# Backplane_extRefV2.net
KiCad netlist of a schematic drawn in EAGLE
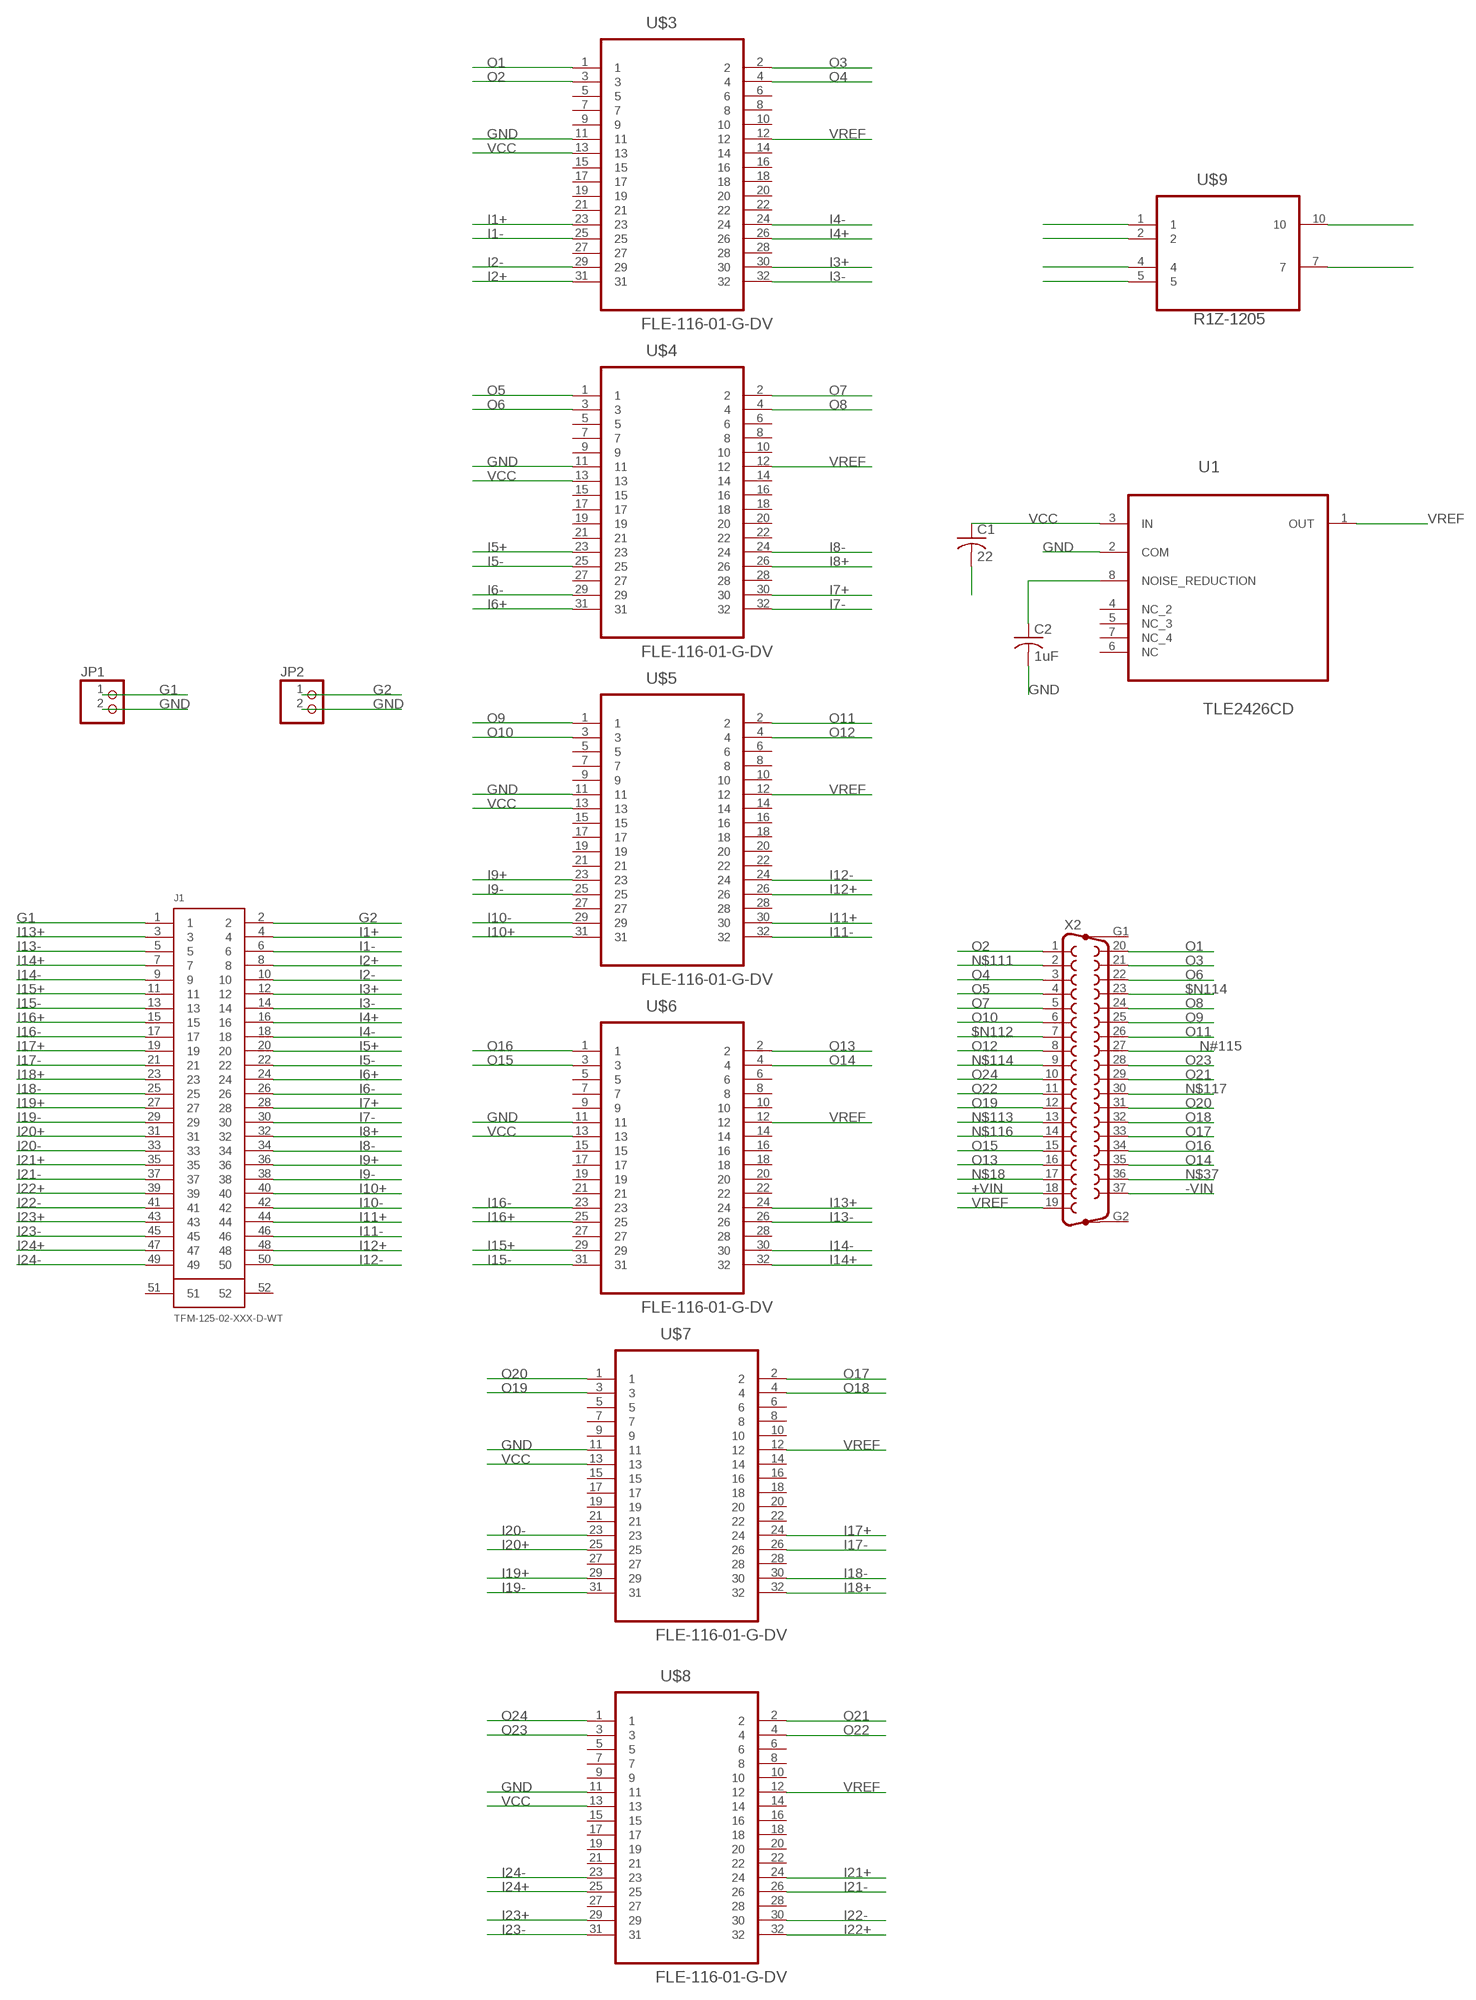
[diagram p0: schematic, sheet 1]

(export (version "E")
  (design (tool "Eeschema 10.0.6"))
  (components
    (comp (ref "C1")
      (value "22")
      (footprint "eagle-import:C0805")
      (libsource (lib "eagle-import") (part "C-USC0805"))
    )
    (comp (ref "C2")
      (value "1uF")
      (footprint "eagle-import:C0805")
      (libsource (lib "eagle-import") (part "C-USC0805"))
    )
    (comp (ref "J1")
      (value "TFM-125-02-XXX-D-WT")
      (footprint "eagle-import:TFM-125-02-XXX-D-WT")
      (libsource (lib "eagle-import") (part "TFM-125-02-XXX-D-WT"))
    )
    (comp (ref "JP1")
      (value "PINHD-1X2")
      (footprint "eagle-import:1X02")
      (libsource (lib "eagle-import") (part "PINHD-1X2"))
    )
    (comp (ref "JP2")
      (value "PINHD-1X2")
      (footprint "eagle-import:1X02")
      (libsource (lib "eagle-import") (part "PINHD-1X2"))
    )
    (comp (ref "U$3")
      (value "FLE-116-01-G-DV")
      (footprint "eagle-import:SAMTEC_FLE-116-01-G-DV")
      (libsource (lib "eagle-import") (part "FLE-116-01-G-DV"))
    )
    (comp (ref "U$4")
      (value "FLE-116-01-G-DV")
      (footprint "eagle-import:SAMTEC_FLE-116-01-G-DV")
      (libsource (lib "eagle-import") (part "FLE-116-01-G-DV"))
    )
    (comp (ref "U$5")
      (value "FLE-116-01-G-DV")
      (footprint "eagle-import:SAMTEC_FLE-116-01-G-DV")
      (libsource (lib "eagle-import") (part "FLE-116-01-G-DV"))
    )
    (comp (ref "U$6")
      (value "FLE-116-01-G-DV")
      (footprint "eagle-import:SAMTEC_FLE-116-01-G-DV")
      (libsource (lib "eagle-import") (part "FLE-116-01-G-DV"))
    )
    (comp (ref "U$7")
      (value "FLE-116-01-G-DV")
      (footprint "eagle-import:SAMTEC_FLE-116-01-G-DV")
      (libsource (lib "eagle-import") (part "FLE-116-01-G-DV"))
    )
    (comp (ref "U$8")
      (value "FLE-116-01-G-DV")
      (footprint "eagle-import:SAMTEC_FLE-116-01-G-DV")
      (libsource (lib "eagle-import") (part "FLE-116-01-G-DV"))
    )
    (comp (ref "U$9")
      (value "R1Z-1205")
      (footprint "eagle-import:R1Z-1205")
      (libsource (lib "eagle-import") (part "R1Z-1205"))
    )
    (comp (ref "U1")
      (value "TLE2426CD")
      (footprint "eagle-import:SOIC127P600X175-8N")
      (libsource (lib "eagle-import") (part "TLE2426CD"))
    )
    (comp (ref "X2")
      (value "F37HP")
      (footprint "eagle-import:F37HP")
      (libsource (lib "eagle-import") (part "F37HP"))
    )
  )
  (nets
    (net (code "1") (name "/$N112") (class "Default")
      (node (ref "X2") (pin "7") (pinfunction "7_7") (pintype "passive"))
    )
    (net (code "2") (name "/$N114") (class "Default")
      (node (ref "X2") (pin "23") (pinfunction "23_23") (pintype "passive"))
    )
    (net (code "3") (name "/+VIN") (class "Default")
      (node (ref "U$9") (pin "2") (pinfunction "2_2") (pintype "passive"))
      (node (ref "X2") (pin "18") (pinfunction "18_18") (pintype "passive"))
    )
    (net (code "4") (name "/-VIN") (class "Default")
      (node (ref "U$9") (pin "1") (pinfunction "1_1") (pintype "passive"))
      (node (ref "X2") (pin "37") (pinfunction "37_37") (pintype "passive"))
    )
    (net (code "5") (name "/G1") (class "Default")
      (node (ref "J1") (pin "1") (pinfunction "1_1") (pintype "bidirectional"))
      (node (ref "JP1") (pin "1") (pinfunction "1_1") (pintype "passive"))
    )
    (net (code "6") (name "/G2") (class "Default")
      (node (ref "J1") (pin "2") (pinfunction "2_2") (pintype "bidirectional"))
      (node (ref "JP2") (pin "1") (pinfunction "1_1") (pintype "passive"))
    )
    (net (code "7") (name "/GND") (class "Default")
      (node (ref "C1") (pin "2") (pinfunction "2_2") (pintype "passive"))
      (node (ref "C2") (pin "2") (pinfunction "2_2") (pintype "passive"))
      (node (ref "JP1") (pin "2") (pinfunction "2_2") (pintype "passive"))
      (node (ref "JP2") (pin "2") (pinfunction "2_2") (pintype "passive"))
      (node (ref "U$3") (pin "11") (pinfunction "11_11") (pintype "passive"))
      (node (ref "U$4") (pin "11") (pinfunction "11_11") (pintype "passive"))
      (node (ref "U$5") (pin "11") (pinfunction "11_11") (pintype "passive"))
      (node (ref "U$6") (pin "11") (pinfunction "11_11") (pintype "passive"))
      (node (ref "U$7") (pin "11") (pinfunction "11_11") (pintype "passive"))
      (node (ref "U$8") (pin "11") (pinfunction "11_11") (pintype "passive"))
      (node (ref "U$9") (pin "4") (pinfunction "4_4") (pintype "passive"))
      (node (ref "U$9") (pin "5") (pinfunction "5_5") (pintype "passive"))
      (node (ref "U1") (pin "2") (pinfunction "COM_2") (pintype "passive"))
    )
    (net (code "8") (name "/I1+") (class "Default")
      (node (ref "J1") (pin "4") (pinfunction "4_4") (pintype "bidirectional"))
      (node (ref "U$3") (pin "23") (pinfunction "23_23") (pintype "passive"))
    )
    (net (code "9") (name "/I1-") (class "Default")
      (node (ref "J1") (pin "6") (pinfunction "6_6") (pintype "bidirectional"))
      (node (ref "U$3") (pin "25") (pinfunction "25_25") (pintype "passive"))
    )
    (net (code "10") (name "/I2+") (class "Default")
      (node (ref "J1") (pin "8") (pinfunction "8_8") (pintype "bidirectional"))
      (node (ref "U$3") (pin "31") (pinfunction "31_31") (pintype "passive"))
    )
    (net (code "11") (name "/I2-") (class "Default")
      (node (ref "J1") (pin "10") (pinfunction "10_10") (pintype "bidirectional"))
      (node (ref "U$3") (pin "29") (pinfunction "29_29") (pintype "passive"))
    )
    (net (code "12") (name "/I3+") (class "Default")
      (node (ref "J1") (pin "12") (pinfunction "12_12") (pintype "bidirectional"))
      (node (ref "U$3") (pin "30") (pinfunction "30_30") (pintype "passive"))
    )
    (net (code "13") (name "/I3-") (class "Default")
      (node (ref "J1") (pin "14") (pinfunction "14_14") (pintype "bidirectional"))
      (node (ref "U$3") (pin "32") (pinfunction "32_32") (pintype "passive"))
    )
    (net (code "14") (name "/I4+") (class "Default")
      (node (ref "J1") (pin "16") (pinfunction "16_16") (pintype "bidirectional"))
      (node (ref "U$3") (pin "26") (pinfunction "26_26") (pintype "passive"))
    )
    (net (code "15") (name "/I4-") (class "Default")
      (node (ref "J1") (pin "18") (pinfunction "18_18") (pintype "bidirectional"))
      (node (ref "U$3") (pin "24") (pinfunction "24_24") (pintype "passive"))
    )
    (net (code "16") (name "/I5+") (class "Default")
      (node (ref "J1") (pin "20") (pinfunction "20_20") (pintype "bidirectional"))
      (node (ref "U$4") (pin "23") (pinfunction "23_23") (pintype "passive"))
    )
    (net (code "17") (name "/I5-") (class "Default")
      (node (ref "J1") (pin "22") (pinfunction "22_22") (pintype "bidirectional"))
      (node (ref "U$4") (pin "25") (pinfunction "25_25") (pintype "passive"))
    )
    (net (code "18") (name "/I6+") (class "Default")
      (node (ref "J1") (pin "24") (pinfunction "24_24") (pintype "bidirectional"))
      (node (ref "U$4") (pin "31") (pinfunction "31_31") (pintype "passive"))
    )
    (net (code "19") (name "/I6-") (class "Default")
      (node (ref "J1") (pin "26") (pinfunction "26_26") (pintype "bidirectional"))
      (node (ref "U$4") (pin "29") (pinfunction "29_29") (pintype "passive"))
    )
    (net (code "20") (name "/I7+") (class "Default")
      (node (ref "J1") (pin "28") (pinfunction "28_28") (pintype "bidirectional"))
      (node (ref "U$4") (pin "30") (pinfunction "30_30") (pintype "passive"))
    )
    (net (code "21") (name "/I7-") (class "Default")
      (node (ref "J1") (pin "30") (pinfunction "30_30") (pintype "bidirectional"))
      (node (ref "U$4") (pin "32") (pinfunction "32_32") (pintype "passive"))
    )
    (net (code "22") (name "/I8+") (class "Default")
      (node (ref "J1") (pin "32") (pinfunction "32_32") (pintype "bidirectional"))
      (node (ref "U$4") (pin "26") (pinfunction "26_26") (pintype "passive"))
    )
    (net (code "23") (name "/I8-") (class "Default")
      (node (ref "J1") (pin "34") (pinfunction "34_34") (pintype "bidirectional"))
      (node (ref "U$4") (pin "24") (pinfunction "24_24") (pintype "passive"))
    )
    (net (code "24") (name "/I9+") (class "Default")
      (node (ref "J1") (pin "36") (pinfunction "36_36") (pintype "bidirectional"))
      (node (ref "U$5") (pin "23") (pinfunction "23_23") (pintype "passive"))
    )
    (net (code "25") (name "/I9-") (class "Default")
      (node (ref "J1") (pin "38") (pinfunction "38_38") (pintype "bidirectional"))
      (node (ref "U$5") (pin "25") (pinfunction "25_25") (pintype "passive"))
    )
    (net (code "26") (name "/I10+") (class "Default")
      (node (ref "J1") (pin "40") (pinfunction "40_40") (pintype "bidirectional"))
      (node (ref "U$5") (pin "31") (pinfunction "31_31") (pintype "passive"))
    )
    (net (code "27") (name "/I10-") (class "Default")
      (node (ref "J1") (pin "42") (pinfunction "42_42") (pintype "bidirectional"))
      (node (ref "U$5") (pin "29") (pinfunction "29_29") (pintype "passive"))
    )
    (net (code "28") (name "/I11+") (class "Default")
      (node (ref "J1") (pin "44") (pinfunction "44_44") (pintype "bidirectional"))
      (node (ref "U$5") (pin "30") (pinfunction "30_30") (pintype "passive"))
    )
    (net (code "29") (name "/I11-") (class "Default")
      (node (ref "J1") (pin "46") (pinfunction "46_46") (pintype "bidirectional"))
      (node (ref "U$5") (pin "32") (pinfunction "32_32") (pintype "passive"))
    )
    (net (code "30") (name "/I12+") (class "Default")
      (node (ref "J1") (pin "48") (pinfunction "48_48") (pintype "bidirectional"))
      (node (ref "U$5") (pin "26") (pinfunction "26_26") (pintype "passive"))
    )
    (net (code "31") (name "/I12-") (class "Default")
      (node (ref "J1") (pin "50") (pinfunction "50_50") (pintype "bidirectional"))
      (node (ref "U$5") (pin "24") (pinfunction "24_24") (pintype "passive"))
    )
    (net (code "32") (name "/I13+") (class "Default")
      (node (ref "J1") (pin "3") (pinfunction "3_3") (pintype "bidirectional"))
      (node (ref "U$6") (pin "24") (pinfunction "24_24") (pintype "passive"))
    )
    (net (code "33") (name "/I13-") (class "Default")
      (node (ref "J1") (pin "5") (pinfunction "5_5") (pintype "bidirectional"))
      (node (ref "U$6") (pin "26") (pinfunction "26_26") (pintype "passive"))
    )
    (net (code "34") (name "/I14+") (class "Default")
      (node (ref "J1") (pin "7") (pinfunction "7_7") (pintype "bidirectional"))
      (node (ref "U$6") (pin "32") (pinfunction "32_32") (pintype "passive"))
    )
    (net (code "35") (name "/I14-") (class "Default")
      (node (ref "J1") (pin "9") (pinfunction "9_9") (pintype "bidirectional"))
      (node (ref "U$6") (pin "30") (pinfunction "30_30") (pintype "passive"))
    )
    (net (code "36") (name "/I15+") (class "Default")
      (node (ref "J1") (pin "11") (pinfunction "11_11") (pintype "bidirectional"))
      (node (ref "U$6") (pin "29") (pinfunction "29_29") (pintype "passive"))
    )
    (net (code "37") (name "/I15-") (class "Default")
      (node (ref "J1") (pin "13") (pinfunction "13_13") (pintype "bidirectional"))
      (node (ref "U$6") (pin "31") (pinfunction "31_31") (pintype "passive"))
    )
    (net (code "38") (name "/I16+") (class "Default")
      (node (ref "J1") (pin "15") (pinfunction "15_15") (pintype "bidirectional"))
      (node (ref "U$6") (pin "25") (pinfunction "25_25") (pintype "passive"))
    )
    (net (code "39") (name "/I16-") (class "Default")
      (node (ref "J1") (pin "17") (pinfunction "17_17") (pintype "bidirectional"))
      (node (ref "U$6") (pin "23") (pinfunction "23_23") (pintype "passive"))
    )
    (net (code "40") (name "/I17+") (class "Default")
      (node (ref "J1") (pin "19") (pinfunction "19_19") (pintype "bidirectional"))
      (node (ref "U$7") (pin "24") (pinfunction "24_24") (pintype "passive"))
    )
    (net (code "41") (name "/I17-") (class "Default")
      (node (ref "J1") (pin "21") (pinfunction "21_21") (pintype "bidirectional"))
      (node (ref "U$7") (pin "26") (pinfunction "26_26") (pintype "passive"))
    )
    (net (code "42") (name "/I18+") (class "Default")
      (node (ref "J1") (pin "23") (pinfunction "23_23") (pintype "bidirectional"))
      (node (ref "U$7") (pin "32") (pinfunction "32_32") (pintype "passive"))
    )
    (net (code "43") (name "/I18-") (class "Default")
      (node (ref "J1") (pin "25") (pinfunction "25_25") (pintype "bidirectional"))
      (node (ref "U$7") (pin "30") (pinfunction "30_30") (pintype "passive"))
    )
    (net (code "44") (name "/I19+") (class "Default")
      (node (ref "J1") (pin "27") (pinfunction "27_27") (pintype "bidirectional"))
      (node (ref "U$7") (pin "29") (pinfunction "29_29") (pintype "passive"))
    )
    (net (code "45") (name "/I19-") (class "Default")
      (node (ref "J1") (pin "29") (pinfunction "29_29") (pintype "bidirectional"))
      (node (ref "U$7") (pin "31") (pinfunction "31_31") (pintype "passive"))
    )
    (net (code "46") (name "/I20+") (class "Default")
      (node (ref "J1") (pin "31") (pinfunction "31_31") (pintype "bidirectional"))
      (node (ref "U$7") (pin "25") (pinfunction "25_25") (pintype "passive"))
    )
    (net (code "47") (name "/I20-") (class "Default")
      (node (ref "J1") (pin "33") (pinfunction "33_33") (pintype "bidirectional"))
      (node (ref "U$7") (pin "23") (pinfunction "23_23") (pintype "passive"))
    )
    (net (code "48") (name "/I21+") (class "Default")
      (node (ref "J1") (pin "35") (pinfunction "35_35") (pintype "bidirectional"))
      (node (ref "U$8") (pin "24") (pinfunction "24_24") (pintype "passive"))
    )
    (net (code "49") (name "/I21-") (class "Default")
      (node (ref "J1") (pin "37") (pinfunction "37_37") (pintype "bidirectional"))
      (node (ref "U$8") (pin "26") (pinfunction "26_26") (pintype "passive"))
    )
    (net (code "50") (name "/I22+") (class "Default")
      (node (ref "J1") (pin "39") (pinfunction "39_39") (pintype "bidirectional"))
      (node (ref "U$8") (pin "32") (pinfunction "32_32") (pintype "passive"))
    )
    (net (code "51") (name "/I22-") (class "Default")
      (node (ref "J1") (pin "41") (pinfunction "41_41") (pintype "bidirectional"))
      (node (ref "U$8") (pin "30") (pinfunction "30_30") (pintype "passive"))
    )
    (net (code "52") (name "/I23+") (class "Default")
      (node (ref "J1") (pin "43") (pinfunction "43_43") (pintype "bidirectional"))
      (node (ref "U$8") (pin "29") (pinfunction "29_29") (pintype "passive"))
    )
    (net (code "53") (name "/I23-") (class "Default")
      (node (ref "J1") (pin "45") (pinfunction "45_45") (pintype "bidirectional"))
      (node (ref "U$8") (pin "31") (pinfunction "31_31") (pintype "passive"))
    )
    (net (code "54") (name "/I24+") (class "Default")
      (node (ref "J1") (pin "47") (pinfunction "47_47") (pintype "bidirectional"))
      (node (ref "U$8") (pin "25") (pinfunction "25_25") (pintype "passive"))
    )
    (net (code "55") (name "/I24-") (class "Default")
      (node (ref "J1") (pin "49") (pinfunction "49_49") (pintype "bidirectional"))
      (node (ref "U$8") (pin "23") (pinfunction "23_23") (pintype "passive"))
    )
    (net (code "56") (name "/N#115") (class "Default")
      (node (ref "X2") (pin "27") (pinfunction "27_27") (pintype "passive"))
    )
    (net (code "57") (name "/N$18") (class "Default")
      (node (ref "X2") (pin "17") (pinfunction "17_17") (pintype "passive"))
    )
    (net (code "58") (name "/N$37") (class "Default")
      (node (ref "X2") (pin "36") (pinfunction "36_36") (pintype "passive"))
    )
    (net (code "59") (name "/N$111") (class "Default")
      (node (ref "X2") (pin "2") (pinfunction "2_2") (pintype "passive"))
    )
    (net (code "60") (name "/N$113") (class "Default")
      (node (ref "X2") (pin "13") (pinfunction "13_13") (pintype "passive"))
    )
    (net (code "61") (name "/N$114") (class "Default")
      (node (ref "X2") (pin "9") (pinfunction "9_9") (pintype "passive"))
    )
    (net (code "62") (name "/N$116") (class "Default")
      (node (ref "X2") (pin "14") (pinfunction "14_14") (pintype "passive"))
    )
    (net (code "63") (name "/N$117") (class "Default")
      (node (ref "X2") (pin "30") (pinfunction "30_30") (pintype "passive"))
    )
    (net (code "64") (name "/O1") (class "Default")
      (node (ref "U$3") (pin "1") (pinfunction "1_1") (pintype "passive"))
      (node (ref "X2") (pin "20") (pinfunction "20_20") (pintype "passive"))
    )
    (net (code "65") (name "/O2") (class "Default")
      (node (ref "U$3") (pin "3") (pinfunction "3_3") (pintype "passive"))
      (node (ref "X2") (pin "1") (pinfunction "1_1") (pintype "passive"))
    )
    (net (code "66") (name "/O3") (class "Default")
      (node (ref "U$3") (pin "2") (pinfunction "2_2") (pintype "passive"))
      (node (ref "X2") (pin "21") (pinfunction "21_21") (pintype "passive"))
    )
    (net (code "67") (name "/O4") (class "Default")
      (node (ref "U$3") (pin "4") (pinfunction "4_4") (pintype "passive"))
      (node (ref "X2") (pin "3") (pinfunction "3_3") (pintype "passive"))
    )
    (net (code "68") (name "/O5") (class "Default")
      (node (ref "U$4") (pin "1") (pinfunction "1_1") (pintype "passive"))
      (node (ref "X2") (pin "4") (pinfunction "4_4") (pintype "passive"))
    )
    (net (code "69") (name "/O6") (class "Default")
      (node (ref "U$4") (pin "3") (pinfunction "3_3") (pintype "passive"))
      (node (ref "X2") (pin "22") (pinfunction "22_22") (pintype "passive"))
    )
    (net (code "70") (name "/O7") (class "Default")
      (node (ref "U$4") (pin "2") (pinfunction "2_2") (pintype "passive"))
      (node (ref "X2") (pin "5") (pinfunction "5_5") (pintype "passive"))
    )
    (net (code "71") (name "/O8") (class "Default")
      (node (ref "U$4") (pin "4") (pinfunction "4_4") (pintype "passive"))
      (node (ref "X2") (pin "24") (pinfunction "24_24") (pintype "passive"))
    )
    (net (code "72") (name "/O9") (class "Default")
      (node (ref "U$5") (pin "1") (pinfunction "1_1") (pintype "passive"))
      (node (ref "X2") (pin "25") (pinfunction "25_25") (pintype "passive"))
    )
    (net (code "73") (name "/O10") (class "Default")
      (node (ref "U$5") (pin "3") (pinfunction "3_3") (pintype "passive"))
      (node (ref "X2") (pin "6") (pinfunction "6_6") (pintype "passive"))
    )
    (net (code "74") (name "/O11") (class "Default")
      (node (ref "U$5") (pin "2") (pinfunction "2_2") (pintype "passive"))
      (node (ref "X2") (pin "26") (pinfunction "26_26") (pintype "passive"))
    )
    (net (code "75") (name "/O12") (class "Default")
      (node (ref "U$5") (pin "4") (pinfunction "4_4") (pintype "passive"))
      (node (ref "X2") (pin "8") (pinfunction "8_8") (pintype "passive"))
    )
    (net (code "76") (name "/O13") (class "Default")
      (node (ref "U$6") (pin "2") (pinfunction "2_2") (pintype "passive"))
      (node (ref "X2") (pin "16") (pinfunction "16_16") (pintype "passive"))
    )
    (net (code "77") (name "/O14") (class "Default")
      (node (ref "U$6") (pin "4") (pinfunction "4_4") (pintype "passive"))
      (node (ref "X2") (pin "35") (pinfunction "35_35") (pintype "passive"))
    )
    (net (code "78") (name "/O15") (class "Default")
      (node (ref "U$6") (pin "3") (pinfunction "3_3") (pintype "passive"))
      (node (ref "X2") (pin "15") (pinfunction "15_15") (pintype "passive"))
    )
    (net (code "79") (name "/O16") (class "Default")
      (node (ref "U$6") (pin "1") (pinfunction "1_1") (pintype "passive"))
      (node (ref "X2") (pin "34") (pinfunction "34_34") (pintype "passive"))
    )
    (net (code "80") (name "/O17") (class "Default")
      (node (ref "U$7") (pin "2") (pinfunction "2_2") (pintype "passive"))
      (node (ref "X2") (pin "33") (pinfunction "33_33") (pintype "passive"))
    )
    (net (code "81") (name "/O18") (class "Default")
      (node (ref "U$7") (pin "4") (pinfunction "4_4") (pintype "passive"))
      (node (ref "X2") (pin "32") (pinfunction "32_32") (pintype "passive"))
    )
    (net (code "82") (name "/O19") (class "Default")
      (node (ref "U$7") (pin "3") (pinfunction "3_3") (pintype "passive"))
      (node (ref "X2") (pin "12") (pinfunction "12_12") (pintype "passive"))
    )
    (net (code "83") (name "/O20") (class "Default")
      (node (ref "U$7") (pin "1") (pinfunction "1_1") (pintype "passive"))
      (node (ref "X2") (pin "31") (pinfunction "31_31") (pintype "passive"))
    )
    (net (code "84") (name "/O21") (class "Default")
      (node (ref "U$8") (pin "2") (pinfunction "2_2") (pintype "passive"))
      (node (ref "X2") (pin "29") (pinfunction "29_29") (pintype "passive"))
    )
    (net (code "85") (name "/O22") (class "Default")
      (node (ref "U$8") (pin "4") (pinfunction "4_4") (pintype "passive"))
      (node (ref "X2") (pin "11") (pinfunction "11_11") (pintype "passive"))
    )
    (net (code "86") (name "/O23") (class "Default")
      (node (ref "U$8") (pin "3") (pinfunction "3_3") (pintype "passive"))
      (node (ref "X2") (pin "28") (pinfunction "28_28") (pintype "passive"))
    )
    (net (code "87") (name "/O24") (class "Default")
      (node (ref "U$8") (pin "1") (pinfunction "1_1") (pintype "passive"))
      (node (ref "X2") (pin "10") (pinfunction "10_10") (pintype "passive"))
    )
    (net (code "88") (name "/VCC") (class "Default")
      (node (ref "C1") (pin "1") (pinfunction "1_1") (pintype "passive"))
      (node (ref "U$3") (pin "13") (pinfunction "13_13") (pintype "passive"))
      (node (ref "U$4") (pin "13") (pinfunction "13_13") (pintype "passive"))
      (node (ref "U$5") (pin "13") (pinfunction "13_13") (pintype "passive"))
      (node (ref "U$6") (pin "13") (pinfunction "13_13") (pintype "passive"))
      (node (ref "U$7") (pin "13") (pinfunction "13_13") (pintype "passive"))
      (node (ref "U$8") (pin "13") (pinfunction "13_13") (pintype "passive"))
      (node (ref "U$9") (pin "7") (pinfunction "7_7") (pintype "passive"))
      (node (ref "U1") (pin "3") (pinfunction "IN_3") (pintype "input"))
    )
    (net (code "89") (name "/VREF") (class "Default")
      (node (ref "U$3") (pin "12") (pinfunction "12_12") (pintype "passive"))
      (node (ref "U$4") (pin "12") (pinfunction "12_12") (pintype "passive"))
      (node (ref "U$5") (pin "12") (pinfunction "12_12") (pintype "passive"))
      (node (ref "U$6") (pin "12") (pinfunction "12_12") (pintype "passive"))
      (node (ref "U$7") (pin "12") (pinfunction "12_12") (pintype "passive"))
      (node (ref "U$8") (pin "12") (pinfunction "12_12") (pintype "passive"))
      (node (ref "U1") (pin "1") (pinfunction "OUT_1") (pintype "output"))
      (node (ref "X2") (pin "19") (pinfunction "19_19") (pintype "passive"))
    )
    (net (code "90") (name "Net-(U1-NOISE_REDUCTION)") (class "Default")
      (node (ref "C2") (pin "1") (pinfunction "1_1") (pintype "passive"))
      (node (ref "U1") (pin "8") (pinfunction "NOISE_REDUCTION_8") (pintype "passive"))
    )
    (net (code "91") (name "unconnected-(J1-Pad51)") (class "Default")
      (node (ref "J1") (pin "51") (pinfunction "51_51") (pintype "bidirectional"))
    )
    (net (code "92") (name "unconnected-(J1-Pad52)") (class "Default")
      (node (ref "J1") (pin "52") (pinfunction "52_52") (pintype "bidirectional"))
    )
    (net (code "93") (name "unconnected-(U$3-Pad5)") (class "Default")
      (node (ref "U$3") (pin "5") (pinfunction "5_5") (pintype "passive"))
    )
    (net (code "94") (name "unconnected-(U$3-Pad6)") (class "Default")
      (node (ref "U$3") (pin "6") (pinfunction "6_6") (pintype "passive"))
    )
    (net (code "95") (name "unconnected-(U$3-Pad7)") (class "Default")
      (node (ref "U$3") (pin "7") (pinfunction "7_7") (pintype "passive"))
    )
    (net (code "96") (name "unconnected-(U$3-Pad8)") (class "Default")
      (node (ref "U$3") (pin "8") (pinfunction "8_8") (pintype "passive"))
    )
    (net (code "97") (name "unconnected-(U$3-Pad9)") (class "Default")
      (node (ref "U$3") (pin "9") (pinfunction "9_9") (pintype "passive"))
    )
    (net (code "98") (name "unconnected-(U$3-Pad10)") (class "Default")
      (node (ref "U$3") (pin "10") (pinfunction "10_10") (pintype "passive"))
    )
    (net (code "99") (name "unconnected-(U$3-Pad14)") (class "Default")
      (node (ref "U$3") (pin "14") (pinfunction "14_14") (pintype "passive"))
    )
    (net (code "100") (name "unconnected-(U$3-Pad15)") (class "Default")
      (node (ref "U$3") (pin "15") (pinfunction "15_15") (pintype "passive"))
    )
    (net (code "101") (name "unconnected-(U$3-Pad16)") (class "Default")
      (node (ref "U$3") (pin "16") (pinfunction "16_16") (pintype "passive"))
    )
    (net (code "102") (name "unconnected-(U$3-Pad17)") (class "Default")
      (node (ref "U$3") (pin "17") (pinfunction "17_17") (pintype "passive"))
    )
    (net (code "103") (name "unconnected-(U$3-Pad18)") (class "Default")
      (node (ref "U$3") (pin "18") (pinfunction "18_18") (pintype "passive"))
    )
    (net (code "104") (name "unconnected-(U$3-Pad19)") (class "Default")
      (node (ref "U$3") (pin "19") (pinfunction "19_19") (pintype "passive"))
    )
    (net (code "105") (name "unconnected-(U$3-Pad20)") (class "Default")
      (node (ref "U$3") (pin "20") (pinfunction "20_20") (pintype "passive"))
    )
    (net (code "106") (name "unconnected-(U$3-Pad21)") (class "Default")
      (node (ref "U$3") (pin "21") (pinfunction "21_21") (pintype "passive"))
    )
    (net (code "107") (name "unconnected-(U$3-Pad22)") (class "Default")
      (node (ref "U$3") (pin "22") (pinfunction "22_22") (pintype "passive"))
    )
    (net (code "108") (name "unconnected-(U$3-Pad27)") (class "Default")
      (node (ref "U$3") (pin "27") (pinfunction "27_27") (pintype "passive"))
    )
    (net (code "109") (name "unconnected-(U$3-Pad28)") (class "Default")
      (node (ref "U$3") (pin "28") (pinfunction "28_28") (pintype "passive"))
    )
    (net (code "110") (name "unconnected-(U$4-Pad5)") (class "Default")
      (node (ref "U$4") (pin "5") (pinfunction "5_5") (pintype "passive"))
    )
    (net (code "111") (name "unconnected-(U$4-Pad6)") (class "Default")
      (node (ref "U$4") (pin "6") (pinfunction "6_6") (pintype "passive"))
    )
    (net (code "112") (name "unconnected-(U$4-Pad7)") (class "Default")
      (node (ref "U$4") (pin "7") (pinfunction "7_7") (pintype "passive"))
    )
    (net (code "113") (name "unconnected-(U$4-Pad8)") (class "Default")
      (node (ref "U$4") (pin "8") (pinfunction "8_8") (pintype "passive"))
    )
    (net (code "114") (name "unconnected-(U$4-Pad9)") (class "Default")
      (node (ref "U$4") (pin "9") (pinfunction "9_9") (pintype "passive"))
    )
    (net (code "115") (name "unconnected-(U$4-Pad10)") (class "Default")
      (node (ref "U$4") (pin "10") (pinfunction "10_10") (pintype "passive"))
    )
    (net (code "116") (name "unconnected-(U$4-Pad14)") (class "Default")
      (node (ref "U$4") (pin "14") (pinfunction "14_14") (pintype "passive"))
    )
    (net (code "117") (name "unconnected-(U$4-Pad15)") (class "Default")
      (node (ref "U$4") (pin "15") (pinfunction "15_15") (pintype "passive"))
    )
    (net (code "118") (name "unconnected-(U$4-Pad16)") (class "Default")
      (node (ref "U$4") (pin "16") (pinfunction "16_16") (pintype "passive"))
    )
    (net (code "119") (name "unconnected-(U$4-Pad17)") (class "Default")
      (node (ref "U$4") (pin "17") (pinfunction "17_17") (pintype "passive"))
    )
    (net (code "120") (name "unconnected-(U$4-Pad18)") (class "Default")
      (node (ref "U$4") (pin "18") (pinfunction "18_18") (pintype "passive"))
    )
    (net (code "121") (name "unconnected-(U$4-Pad19)") (class "Default")
      (node (ref "U$4") (pin "19") (pinfunction "19_19") (pintype "passive"))
    )
    (net (code "122") (name "unconnected-(U$4-Pad20)") (class "Default")
      (node (ref "U$4") (pin "20") (pinfunction "20_20") (pintype "passive"))
    )
    (net (code "123") (name "unconnected-(U$4-Pad21)") (class "Default")
      (node (ref "U$4") (pin "21") (pinfunction "21_21") (pintype "passive"))
    )
    (net (code "124") (name "unconnected-(U$4-Pad22)") (class "Default")
      (node (ref "U$4") (pin "22") (pinfunction "22_22") (pintype "passive"))
    )
    (net (code "125") (name "unconnected-(U$4-Pad27)") (class "Default")
      (node (ref "U$4") (pin "27") (pinfunction "27_27") (pintype "passive"))
    )
    (net (code "126") (name "unconnected-(U$4-Pad28)") (class "Default")
      (node (ref "U$4") (pin "28") (pinfunction "28_28") (pintype "passive"))
    )
    (net (code "127") (name "unconnected-(U$5-Pad5)") (class "Default")
      (node (ref "U$5") (pin "5") (pinfunction "5_5") (pintype "passive"))
    )
    (net (code "128") (name "unconnected-(U$5-Pad6)") (class "Default")
      (node (ref "U$5") (pin "6") (pinfunction "6_6") (pintype "passive"))
    )
    (net (code "129") (name "unconnected-(U$5-Pad7)") (class "Default")
      (node (ref "U$5") (pin "7") (pinfunction "7_7") (pintype "passive"))
    )
    (net (code "130") (name "unconnected-(U$5-Pad8)") (class "Default")
      (node (ref "U$5") (pin "8") (pinfunction "8_8") (pintype "passive"))
    )
    (net (code "131") (name "unconnected-(U$5-Pad9)") (class "Default")
      (node (ref "U$5") (pin "9") (pinfunction "9_9") (pintype "passive"))
    )
    (net (code "132") (name "unconnected-(U$5-Pad10)") (class "Default")
      (node (ref "U$5") (pin "10") (pinfunction "10_10") (pintype "passive"))
    )
    (net (code "133") (name "unconnected-(U$5-Pad14)") (class "Default")
      (node (ref "U$5") (pin "14") (pinfunction "14_14") (pintype "passive"))
    )
    (net (code "134") (name "unconnected-(U$5-Pad15)") (class "Default")
      (node (ref "U$5") (pin "15") (pinfunction "15_15") (pintype "passive"))
    )
    (net (code "135") (name "unconnected-(U$5-Pad16)") (class "Default")
      (node (ref "U$5") (pin "16") (pinfunction "16_16") (pintype "passive"))
    )
    (net (code "136") (name "unconnected-(U$5-Pad17)") (class "Default")
      (node (ref "U$5") (pin "17") (pinfunction "17_17") (pintype "passive"))
    )
    (net (code "137") (name "unconnected-(U$5-Pad18)") (class "Default")
      (node (ref "U$5") (pin "18") (pinfunction "18_18") (pintype "passive"))
    )
    (net (code "138") (name "unconnected-(U$5-Pad19)") (class "Default")
      (node (ref "U$5") (pin "19") (pinfunction "19_19") (pintype "passive"))
    )
    (net (code "139") (name "unconnected-(U$5-Pad20)") (class "Default")
      (node (ref "U$5") (pin "20") (pinfunction "20_20") (pintype "passive"))
    )
    (net (code "140") (name "unconnected-(U$5-Pad21)") (class "Default")
      (node (ref "U$5") (pin "21") (pinfunction "21_21") (pintype "passive"))
    )
    (net (code "141") (name "unconnected-(U$5-Pad22)") (class "Default")
      (node (ref "U$5") (pin "22") (pinfunction "22_22") (pintype "passive"))
    )
    (net (code "142") (name "unconnected-(U$5-Pad27)") (class "Default")
      (node (ref "U$5") (pin "27") (pinfunction "27_27") (pintype "passive"))
    )
    (net (code "143") (name "unconnected-(U$5-Pad28)") (class "Default")
      (node (ref "U$5") (pin "28") (pinfunction "28_28") (pintype "passive"))
    )
    (net (code "144") (name "unconnected-(U$6-Pad5)") (class "Default")
      (node (ref "U$6") (pin "5") (pinfunction "5_5") (pintype "passive"))
    )
    (net (code "145") (name "unconnected-(U$6-Pad6)") (class "Default")
      (node (ref "U$6") (pin "6") (pinfunction "6_6") (pintype "passive"))
    )
    (net (code "146") (name "unconnected-(U$6-Pad7)") (class "Default")
      (node (ref "U$6") (pin "7") (pinfunction "7_7") (pintype "passive"))
    )
    (net (code "147") (name "unconnected-(U$6-Pad8)") (class "Default")
      (node (ref "U$6") (pin "8") (pinfunction "8_8") (pintype "passive"))
    )
    (net (code "148") (name "unconnected-(U$6-Pad9)") (class "Default")
      (node (ref "U$6") (pin "9") (pinfunction "9_9") (pintype "passive"))
    )
    (net (code "149") (name "unconnected-(U$6-Pad10)") (class "Default")
      (node (ref "U$6") (pin "10") (pinfunction "10_10") (pintype "passive"))
    )
    (net (code "150") (name "unconnected-(U$6-Pad14)") (class "Default")
      (node (ref "U$6") (pin "14") (pinfunction "14_14") (pintype "passive"))
    )
    (net (code "151") (name "unconnected-(U$6-Pad15)") (class "Default")
      (node (ref "U$6") (pin "15") (pinfunction "15_15") (pintype "passive"))
    )
    (net (code "152") (name "unconnected-(U$6-Pad16)") (class "Default")
      (node (ref "U$6") (pin "16") (pinfunction "16_16") (pintype "passive"))
    )
    (net (code "153") (name "unconnected-(U$6-Pad17)") (class "Default")
      (node (ref "U$6") (pin "17") (pinfunction "17_17") (pintype "passive"))
    )
    (net (code "154") (name "unconnected-(U$6-Pad18)") (class "Default")
      (node (ref "U$6") (pin "18") (pinfunction "18_18") (pintype "passive"))
    )
    (net (code "155") (name "unconnected-(U$6-Pad19)") (class "Default")
      (node (ref "U$6") (pin "19") (pinfunction "19_19") (pintype "passive"))
    )
    (net (code "156") (name "unconnected-(U$6-Pad20)") (class "Default")
      (node (ref "U$6") (pin "20") (pinfunction "20_20") (pintype "passive"))
    )
    (net (code "157") (name "unconnected-(U$6-Pad21)") (class "Default")
      (node (ref "U$6") (pin "21") (pinfunction "21_21") (pintype "passive"))
    )
    (net (code "158") (name "unconnected-(U$6-Pad22)") (class "Default")
      (node (ref "U$6") (pin "22") (pinfunction "22_22") (pintype "passive"))
    )
    (net (code "159") (name "unconnected-(U$6-Pad27)") (class "Default")
      (node (ref "U$6") (pin "27") (pinfunction "27_27") (pintype "passive"))
    )
    (net (code "160") (name "unconnected-(U$6-Pad28)") (class "Default")
      (node (ref "U$6") (pin "28") (pinfunction "28_28") (pintype "passive"))
    )
    (net (code "161") (name "unconnected-(U$7-Pad5)") (class "Default")
      (node (ref "U$7") (pin "5") (pinfunction "5_5") (pintype "passive"))
    )
    (net (code "162") (name "unconnected-(U$7-Pad6)") (class "Default")
      (node (ref "U$7") (pin "6") (pinfunction "6_6") (pintype "passive"))
    )
    (net (code "163") (name "unconnected-(U$7-Pad7)") (class "Default")
      (node (ref "U$7") (pin "7") (pinfunction "7_7") (pintype "passive"))
    )
    (net (code "164") (name "unconnected-(U$7-Pad8)") (class "Default")
      (node (ref "U$7") (pin "8") (pinfunction "8_8") (pintype "passive"))
    )
    (net (code "165") (name "unconnected-(U$7-Pad9)") (class "Default")
      (node (ref "U$7") (pin "9") (pinfunction "9_9") (pintype "passive"))
    )
    (net (code "166") (name "unconnected-(U$7-Pad10)") (class "Default")
      (node (ref "U$7") (pin "10") (pinfunction "10_10") (pintype "passive"))
    )
    (net (code "167") (name "unconnected-(U$7-Pad14)") (class "Default")
      (node (ref "U$7") (pin "14") (pinfunction "14_14") (pintype "passive"))
    )
    (net (code "168") (name "unconnected-(U$7-Pad15)") (class "Default")
      (node (ref "U$7") (pin "15") (pinfunction "15_15") (pintype "passive"))
    )
    (net (code "169") (name "unconnected-(U$7-Pad16)") (class "Default")
      (node (ref "U$7") (pin "16") (pinfunction "16_16") (pintype "passive"))
    )
    (net (code "170") (name "unconnected-(U$7-Pad17)") (class "Default")
      (node (ref "U$7") (pin "17") (pinfunction "17_17") (pintype "passive"))
    )
    (net (code "171") (name "unconnected-(U$7-Pad18)") (class "Default")
      (node (ref "U$7") (pin "18") (pinfunction "18_18") (pintype "passive"))
    )
    (net (code "172") (name "unconnected-(U$7-Pad19)") (class "Default")
      (node (ref "U$7") (pin "19") (pinfunction "19_19") (pintype "passive"))
    )
    (net (code "173") (name "unconnected-(U$7-Pad20)") (class "Default")
      (node (ref "U$7") (pin "20") (pinfunction "20_20") (pintype "passive"))
    )
    (net (code "174") (name "unconnected-(U$7-Pad21)") (class "Default")
      (node (ref "U$7") (pin "21") (pinfunction "21_21") (pintype "passive"))
    )
    (net (code "175") (name "unconnected-(U$7-Pad22)") (class "Default")
      (node (ref "U$7") (pin "22") (pinfunction "22_22") (pintype "passive"))
    )
    (net (code "176") (name "unconnected-(U$7-Pad27)") (class "Default")
      (node (ref "U$7") (pin "27") (pinfunction "27_27") (pintype "passive"))
    )
    (net (code "177") (name "unconnected-(U$7-Pad28)") (class "Default")
      (node (ref "U$7") (pin "28") (pinfunction "28_28") (pintype "passive"))
    )
    (net (code "178") (name "unconnected-(U$8-Pad5)") (class "Default")
      (node (ref "U$8") (pin "5") (pinfunction "5_5") (pintype "passive"))
    )
    (net (code "179") (name "unconnected-(U$8-Pad6)") (class "Default")
      (node (ref "U$8") (pin "6") (pinfunction "6_6") (pintype "passive"))
    )
    (net (code "180") (name "unconnected-(U$8-Pad7)") (class "Default")
      (node (ref "U$8") (pin "7") (pinfunction "7_7") (pintype "passive"))
    )
    (net (code "181") (name "unconnected-(U$8-Pad8)") (class "Default")
      (node (ref "U$8") (pin "8") (pinfunction "8_8") (pintype "passive"))
    )
    (net (code "182") (name "unconnected-(U$8-Pad9)") (class "Default")
      (node (ref "U$8") (pin "9") (pinfunction "9_9") (pintype "passive"))
    )
    (net (code "183") (name "unconnected-(U$8-Pad10)") (class "Default")
      (node (ref "U$8") (pin "10") (pinfunction "10_10") (pintype "passive"))
    )
    (net (code "184") (name "unconnected-(U$8-Pad14)") (class "Default")
      (node (ref "U$8") (pin "14") (pinfunction "14_14") (pintype "passive"))
    )
    (net (code "185") (name "unconnected-(U$8-Pad15)") (class "Default")
      (node (ref "U$8") (pin "15") (pinfunction "15_15") (pintype "passive"))
    )
    (net (code "186") (name "unconnected-(U$8-Pad16)") (class "Default")
      (node (ref "U$8") (pin "16") (pinfunction "16_16") (pintype "passive"))
    )
    (net (code "187") (name "unconnected-(U$8-Pad17)") (class "Default")
      (node (ref "U$8") (pin "17") (pinfunction "17_17") (pintype "passive"))
    )
    (net (code "188") (name "unconnected-(U$8-Pad18)") (class "Default")
      (node (ref "U$8") (pin "18") (pinfunction "18_18") (pintype "passive"))
    )
    (net (code "189") (name "unconnected-(U$8-Pad19)") (class "Default")
      (node (ref "U$8") (pin "19") (pinfunction "19_19") (pintype "passive"))
    )
    (net (code "190") (name "unconnected-(U$8-Pad20)") (class "Default")
      (node (ref "U$8") (pin "20") (pinfunction "20_20") (pintype "passive"))
    )
    (net (code "191") (name "unconnected-(U$8-Pad21)") (class "Default")
      (node (ref "U$8") (pin "21") (pinfunction "21_21") (pintype "passive"))
    )
    (net (code "192") (name "unconnected-(U$8-Pad22)") (class "Default")
      (node (ref "U$8") (pin "22") (pinfunction "22_22") (pintype "passive"))
    )
    (net (code "193") (name "unconnected-(U$8-Pad27)") (class "Default")
      (node (ref "U$8") (pin "27") (pinfunction "27_27") (pintype "passive"))
    )
    (net (code "194") (name "unconnected-(U$8-Pad28)") (class "Default")
      (node (ref "U$8") (pin "28") (pinfunction "28_28") (pintype "passive"))
    )
    (net (code "195") (name "unconnected-(U$9-Pad10)") (class "Default")
      (node (ref "U$9") (pin "10") (pinfunction "10_10") (pintype "passive"))
    )
    (net (code "196") (name "unconnected-(U1-NC-Pad6)") (class "Default")
      (node (ref "U1") (pin "6") (pinfunction "NC_6") (pintype "no_connect"))
    )
    (net (code "197") (name "unconnected-(U1-NC_2-Pad4)") (class "Default")
      (node (ref "U1") (pin "4") (pinfunction "NC_2_4") (pintype "no_connect"))
    )
    (net (code "198") (name "unconnected-(U1-NC_3-Pad5)") (class "Default")
      (node (ref "U1") (pin "5") (pinfunction "NC_3_5") (pintype "no_connect"))
    )
    (net (code "199") (name "unconnected-(U1-NC_4-Pad7)") (class "Default")
      (node (ref "U1") (pin "7") (pinfunction "NC_4_7") (pintype "no_connect"))
    )
    (net (code "200") (name "unconnected-(X2-PadG1)") (class "Default")
      (node (ref "X2") (pin "G1") (pinfunction "G1_G1") (pintype "passive"))
    )
    (net (code "201") (name "unconnected-(X2-PadG2)") (class "Default")
      (node (ref "X2") (pin "G2") (pinfunction "G2_G2") (pintype "passive"))
    )
  )
)
